# ethernet_poe.net
KiCad netlist of a schematic drawn in EAGLE
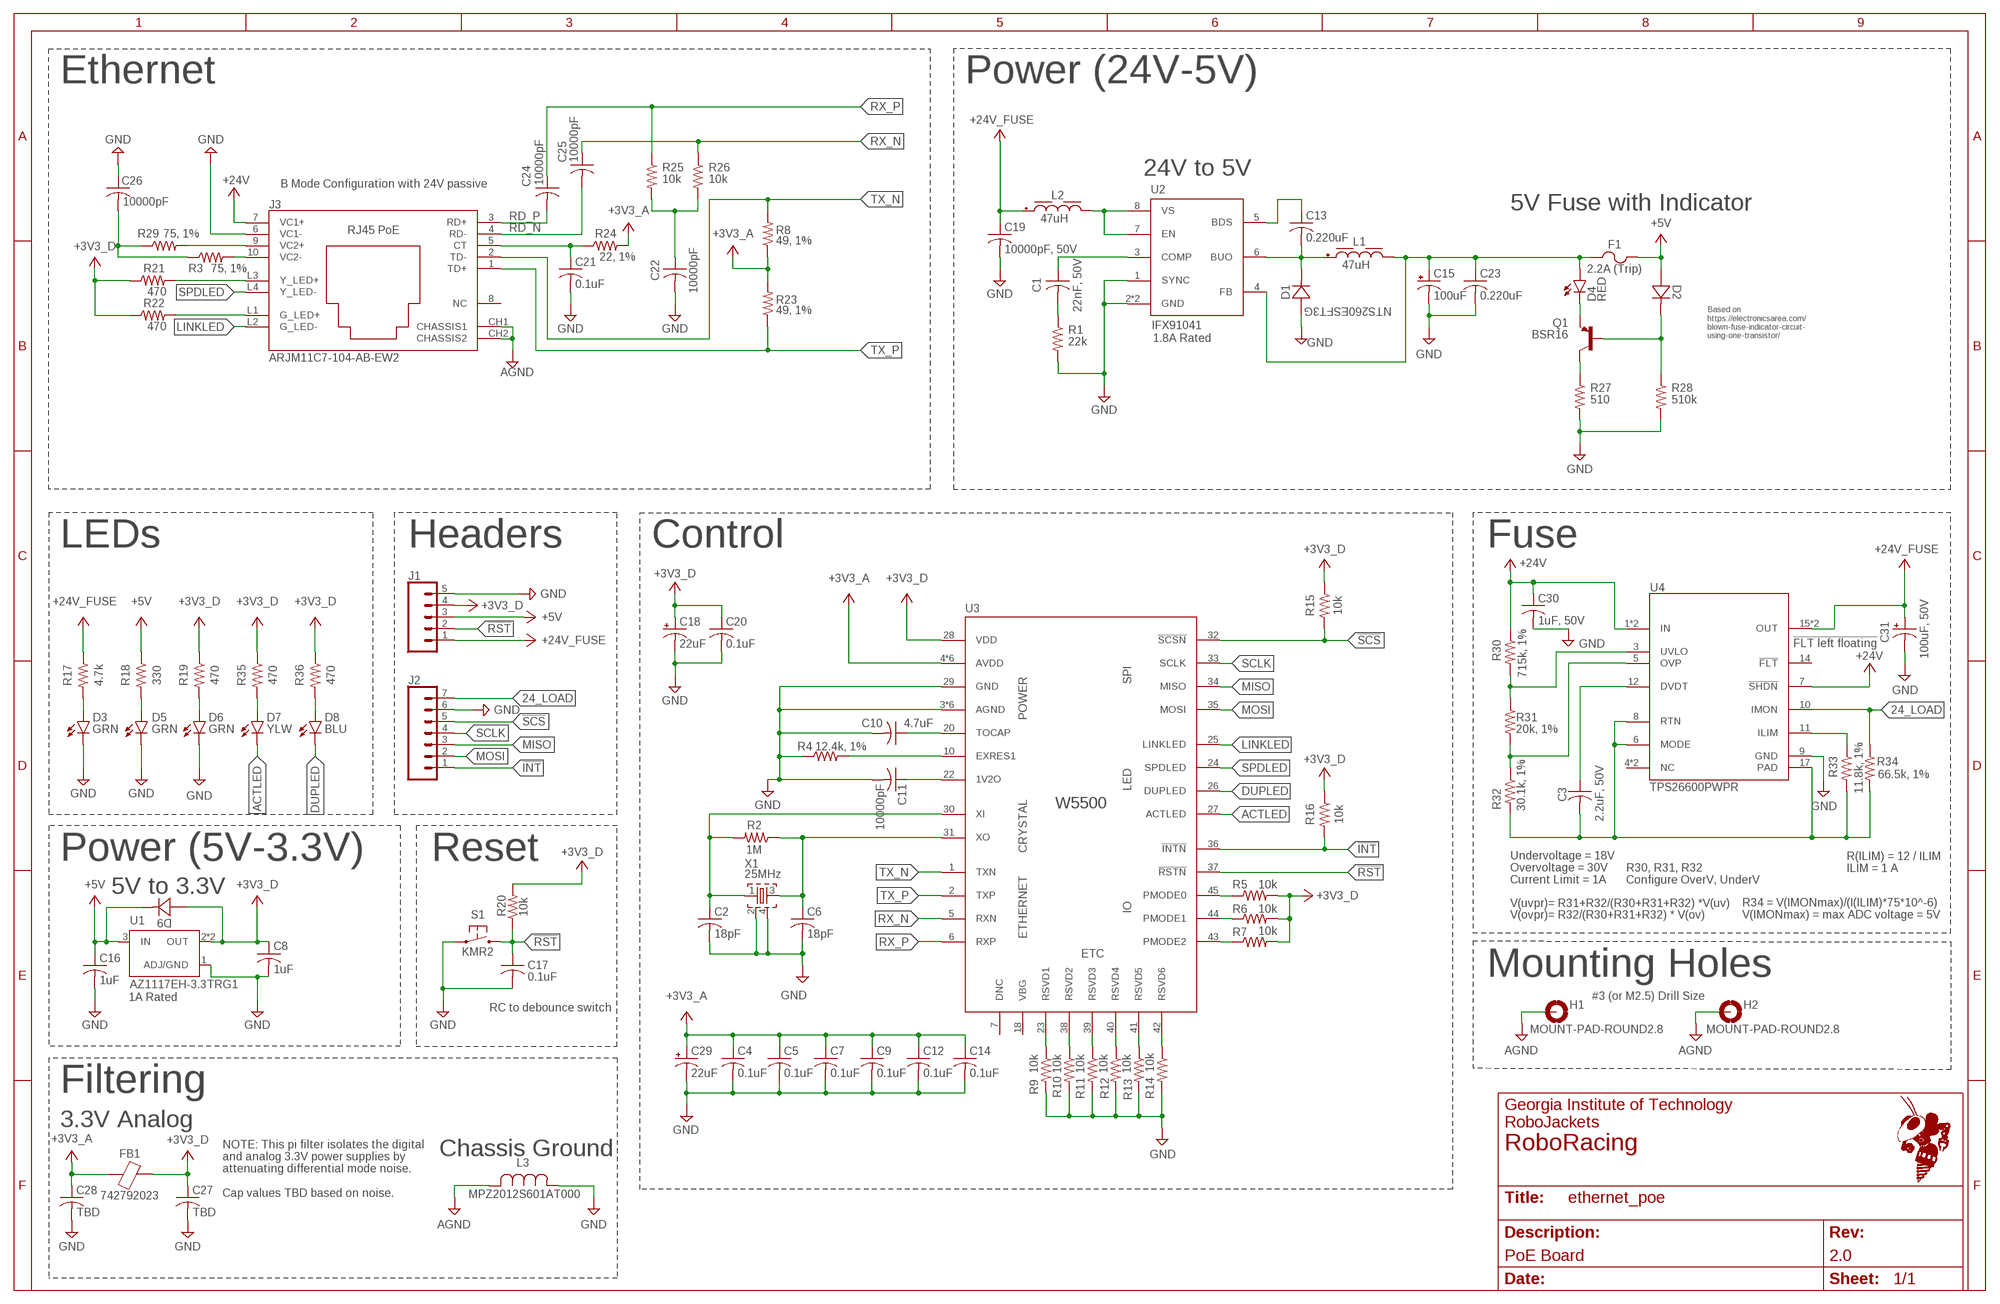
[diagram p0: schematic, sheet 1]

(export (version "E")
  (design (tool "Eeschema 10.0.6"))
  (components
    (comp (ref "C1")
      (value "22nF, 50V")
      (footprint "eagle-import:C0603")
      (libsource (lib "eagle-import") (part "rcl_334_C-USC0603"))
    )
    (comp (ref "C2")
      (value "18pF")
      (footprint "eagle-import:C0603")
      (libsource (lib "eagle-import") (part "rcl_334_C-USC0603"))
    )
    (comp (ref "C3")
      (value "2.2uF, 50V")
      (footprint "eagle-import:C0603")
      (libsource (lib "eagle-import") (part "rcl_334_C-USC0603"))
    )
    (comp (ref "C4")
      (value "0.1uF")
      (footprint "eagle-import:C0402")
      (libsource (lib "eagle-import") (part "C-USC0402"))
    )
    (comp (ref "C5")
      (value "0.1uF")
      (footprint "eagle-import:C0402")
      (libsource (lib "eagle-import") (part "C-USC0402"))
    )
    (comp (ref "C6")
      (value "18pF")
      (footprint "eagle-import:C0603")
      (libsource (lib "eagle-import") (part "rcl_334_C-USC0603"))
    )
    (comp (ref "C7")
      (value "0.1uF")
      (footprint "eagle-import:C0402")
      (libsource (lib "eagle-import") (part "C-USC0402"))
    )
    (comp (ref "C8")
      (value "1uF")
      (footprint "eagle-import:C0603")
      (libsource (lib "eagle-import") (part "rcl_334_C-USC0603"))
    )
    (comp (ref "C9")
      (value "0.1uF")
      (footprint "eagle-import:C0402")
      (libsource (lib "eagle-import") (part "C-USC0402"))
    )
    (comp (ref "C10")
      (value "4.7uF")
      (footprint "eagle-import:C0603")
      (libsource (lib "eagle-import") (part "rcl_334_C-USC0603"))
    )
    (comp (ref "C11")
      (value "10000pF")
      (footprint "eagle-import:C0402")
      (libsource (lib "eagle-import") (part "C-USC0402"))
    )
    (comp (ref "C12")
      (value "0.1uF")
      (footprint "eagle-import:C0402")
      (libsource (lib "eagle-import") (part "C-USC0402"))
    )
    (comp (ref "C13")
      (value "0.220uF")
      (footprint "eagle-import:C0603")
      (libsource (lib "eagle-import") (part "rcl_334_C-USC0603"))
    )
    (comp (ref "C14")
      (value "0.1uF")
      (footprint "eagle-import:C0402")
      (libsource (lib "eagle-import") (part "C-USC0402"))
    )
    (comp (ref "C15")
      (value "100uF")
      (footprint "eagle-import:E2-5")
      (libsource (lib "eagle-import") (part "CPOL-USE2-5"))
    )
    (comp (ref "C16")
      (value "1uF")
      (footprint "eagle-import:C0603")
      (libsource (lib "eagle-import") (part "rcl_334_C-USC0603"))
    )
    (comp (ref "C17")
      (value "0.1uF")
      (footprint "eagle-import:C0603")
      (libsource (lib "eagle-import") (part "rcl_334_C-USC0603"))
    )
    (comp (ref "C18")
      (value "22uF")
      (footprint "eagle-import:E2-5")
      (libsource (lib "eagle-import") (part "CPOL-USE2-5"))
    )
    (comp (ref "C19")
      (value "10000pF, 50V")
      (footprint "eagle-import:C0603")
      (libsource (lib "eagle-import") (part "rcl_334_C-USC0603"))
    )
    (comp (ref "C20")
      (value "0.1uF")
      (footprint "eagle-import:C0603")
      (libsource (lib "eagle-import") (part "rcl_334_C-USC0603"))
    )
    (comp (ref "C21")
      (value "0.1uF")
      (footprint "eagle-import:C0603")
      (libsource (lib "eagle-import") (part "rcl_334_C-USC0603"))
    )
    (comp (ref "C22")
      (value "10000pF")
      (footprint "eagle-import:C0603")
      (libsource (lib "eagle-import") (part "rcl_334_C-USC0603"))
    )
    (comp (ref "C23")
      (value "0.220uF")
      (footprint "eagle-import:C0603")
      (libsource (lib "eagle-import") (part "rcl_334_C-USC0603"))
    )
    (comp (ref "C24")
      (value "10000pF")
      (footprint "eagle-import:C0402")
      (libsource (lib "eagle-import") (part "C-USC0402"))
    )
    (comp (ref "C25")
      (value "10000pF")
      (footprint "eagle-import:C0402")
      (libsource (lib "eagle-import") (part "C-USC0402"))
    )
    (comp (ref "C26")
      (value "10000pF")
      (footprint "eagle-import:C0603")
      (libsource (lib "eagle-import") (part "rcl_334_C-USC0603"))
    )
    (comp (ref "C27")
      (value "TBD")
      (footprint "eagle-import:C0603")
      (libsource (lib "eagle-import") (part "C-USC0603"))
    )
    (comp (ref "C28")
      (value "TBD")
      (footprint "eagle-import:C0603")
      (libsource (lib "eagle-import") (part "C-USC0603"))
    )
    (comp (ref "C29")
      (value "22uF")
      (footprint "eagle-import:PANASONIC_C")
      (libsource (lib "eagle-import") (part "22UF-POLAR-PANASONIC_C-35V-20%"))
    )
    (comp (ref "C30")
      (value "1uF, 50V")
      (footprint "eagle-import:C0603")
      (libsource (lib "eagle-import") (part "rcl_334_C-USC0603"))
    )
    (comp (ref "C31")
      (value "100uF, 50V")
      (footprint "eagle-import:E2-5")
      (libsource (lib "eagle-import") (part "CPOL-USE2-5"))
    )
    (comp (ref "D1")
      (value "NTS260ESFT3G")
      (footprint "eagle-import:DIO_SS26FL")
      (libsource (lib "eagle-import") (part "NTS260ESFT3G"))
    )
    (comp (ref "D2")
      (value "1N4148W-7-F")
      (footprint "eagle-import:SOD123_DIO")
      (libsource (lib "eagle-import") (part "1N4148W-7-F"))
    )
    (comp (ref "D3")
      (value "GRN")
      (footprint "eagle-import:CHIP-LED0603")
      (libsource (lib "eagle-import") (part "LEDCHIP-LED0603"))
    )
    (comp (ref "D4")
      (value "RED")
      (footprint "eagle-import:CHIP-LED0603")
      (libsource (lib "eagle-import") (part "LEDCHIP-LED0603"))
    )
    (comp (ref "D5")
      (value "GRN")
      (footprint "eagle-import:CHIP-LED0603")
      (libsource (lib "eagle-import") (part "LEDCHIP-LED0603"))
    )
    (comp (ref "D6")
      (value "GRN")
      (footprint "eagle-import:CHIP-LED0603")
      (libsource (lib "eagle-import") (part "LEDCHIP-LED0603"))
    )
    (comp (ref "D7")
      (value "YLW")
      (footprint "eagle-import:CHIP-LED0603")
      (libsource (lib "eagle-import") (part "LEDCHIP-LED0603"))
    )
    (comp (ref "D8")
      (value "BLU")
      (footprint "eagle-import:CHIP-LED0603")
      (libsource (lib "eagle-import") (part "LEDCHIP-LED0603"))
    )
    (comp (ref "D9")
      (value "1N4148W-7-F")
      (footprint "eagle-import:SOD123_DIO")
      (libsource (lib "eagle-import") (part "1N4148W-7-F"))
    )
    (comp (ref "F1")
      (value "2.2A (Trip)")
      (footprint "eagle-import:0ZCG_BEL")
      (libsource (lib "eagle-import") (part "0ZCG0110AF2C"))
    )
    (comp (ref "FB1")
      (value "742792023")
      (footprint "eagle-import:0805")
      (libsource (lib "eagle-import") (part "742792023"))
    )
    (comp (ref "H1")
      (value "MOUNT-PAD-ROUND2.8")
      (footprint "eagle-import:2,8-PAD")
      (libsource (lib "eagle-import") (part "MOUNT-PAD-ROUND2.8"))
    )
    (comp (ref "H2")
      (value "MOUNT-PAD-ROUND2.8")
      (footprint "eagle-import:2,8-PAD")
      (libsource (lib "eagle-import") (part "MOUNT-PAD-ROUND2.8"))
    )
    (comp (ref "J1")
      (value "CONN_05")
      (footprint "eagle-import:1X05")
      (libsource (lib "eagle-import") (part "CONN_05"))
    )
    (comp (ref "J2")
      (value "CONN_07")
      (footprint "eagle-import:1X07")
      (libsource (lib "eagle-import") (part "CONN_07"))
    )
    (comp (ref "J3")
      (value "ARJM11C7-104-AB-EW2")
      (footprint "eagle-import:CONN_EW_ABR")
      (libsource (lib "eagle-import") (part "ARJM11C7-104-AB-EW2"))
    )
    (comp (ref "L1")
      (value "47uH")
      (footprint "eagle-import:WE-PD_1260")
      (libsource (lib "eagle-import") (part "WE-PD_1260_744771147"))
    )
    (comp (ref "L2")
      (value "47uH")
      (footprint "eagle-import:WE-PD_7345")
      (libsource (lib "eagle-import") (part "WE-PD_7345_744777147"))
    )
    (comp (ref "L3")
      (value "MPZ2012S601AT000")
      (footprint "eagle-import:IND_2012_TDK")
      (libsource (lib "eagle-import") (part "MPZ2012S601AT000"))
    )
    (comp (ref "Q1")
      (value "BSR16")
      (footprint "eagle-import:SOT-23-3")
      (libsource (lib "eagle-import") (part "BSR16"))
    )
    (comp (ref "R1")
      (value "22k")
      (footprint "eagle-import:R0603")
      (libsource (lib "eagle-import") (part "rcl_334_R-US_R0603"))
    )
    (comp (ref "R2")
      (value "1M")
      (footprint "eagle-import:R0402")
      (libsource (lib "eagle-import") (part "R-US_R0402"))
    )
    (comp (ref "R3")
      (value "75, 1%")
      (footprint "eagle-import:R0603")
      (libsource (lib "eagle-import") (part "rcl_334_R-US_R0603"))
    )
    (comp (ref "R4")
      (value "12.4k, 1%")
      (footprint "eagle-import:R0603")
      (libsource (lib "eagle-import") (part "rcl_334_R-US_R0603"))
    )
    (comp (ref "R5")
      (value "10k")
      (footprint "eagle-import:R0603")
      (libsource (lib "eagle-import") (part "rcl_334_R-US_R0603"))
    )
    (comp (ref "R6")
      (value "10k")
      (footprint "eagle-import:R0603")
      (libsource (lib "eagle-import") (part "rcl_334_R-US_R0603"))
    )
    (comp (ref "R7")
      (value "10k")
      (footprint "eagle-import:R0603")
      (libsource (lib "eagle-import") (part "rcl_334_R-US_R0603"))
    )
    (comp (ref "R8")
      (value "49, 1%")
      (footprint "eagle-import:R0402")
      (libsource (lib "eagle-import") (part "R-US_R0402"))
    )
    (comp (ref "R9")
      (value "10k")
      (footprint "eagle-import:R0603")
      (libsource (lib "eagle-import") (part "rcl_334_R-US_R0603"))
    )
    (comp (ref "R10")
      (value "10k")
      (footprint "eagle-import:R0603")
      (libsource (lib "eagle-import") (part "rcl_334_R-US_R0603"))
    )
    (comp (ref "R11")
      (value "10k")
      (footprint "eagle-import:R0603")
      (libsource (lib "eagle-import") (part "rcl_334_R-US_R0603"))
    )
    (comp (ref "R12")
      (value "10k")
      (footprint "eagle-import:R0603")
      (libsource (lib "eagle-import") (part "rcl_334_R-US_R0603"))
    )
    (comp (ref "R13")
      (value "10k")
      (footprint "eagle-import:R0603")
      (libsource (lib "eagle-import") (part "rcl_334_R-US_R0603"))
    )
    (comp (ref "R14")
      (value "10k")
      (footprint "eagle-import:R0603")
      (libsource (lib "eagle-import") (part "rcl_334_R-US_R0603"))
    )
    (comp (ref "R15")
      (value "10k")
      (footprint "eagle-import:R0603")
      (libsource (lib "eagle-import") (part "rcl_334_R-US_R0603"))
    )
    (comp (ref "R16")
      (value "10k")
      (footprint "eagle-import:R0603")
      (libsource (lib "eagle-import") (part "rcl_334_R-US_R0603"))
    )
    (comp (ref "R17")
      (value "4.7k")
      (footprint "eagle-import:R0603")
      (libsource (lib "eagle-import") (part "rcl_334_R-US_R0603"))
    )
    (comp (ref "R18")
      (value "330")
      (footprint "eagle-import:R0603")
      (libsource (lib "eagle-import") (part "rcl_334_R-US_R0603"))
    )
    (comp (ref "R19")
      (value "470")
      (footprint "eagle-import:R0603")
      (libsource (lib "eagle-import") (part "rcl_334_R-US_R0603"))
    )
    (comp (ref "R20")
      (value "10k")
      (footprint "eagle-import:R0603")
      (libsource (lib "eagle-import") (part "rcl_334_R-US_R0603"))
    )
    (comp (ref "R21")
      (value "470")
      (footprint "eagle-import:R0603")
      (libsource (lib "eagle-import") (part "rcl_334_R-US_R0603"))
    )
    (comp (ref "R22")
      (value "470")
      (footprint "eagle-import:R0603")
      (libsource (lib "eagle-import") (part "rcl_334_R-US_R0603"))
    )
    (comp (ref "R23")
      (value "49, 1%")
      (footprint "eagle-import:R0402")
      (libsource (lib "eagle-import") (part "R-US_R0402"))
    )
    (comp (ref "R24")
      (value "22, 1%")
      (footprint "eagle-import:R0603")
      (libsource (lib "eagle-import") (part "rcl_334_R-US_R0603"))
    )
    (comp (ref "R25")
      (value "10k")
      (footprint "eagle-import:R0603")
      (libsource (lib "eagle-import") (part "rcl_334_R-US_R0603"))
    )
    (comp (ref "R26")
      (value "10k")
      (footprint "eagle-import:R0603")
      (libsource (lib "eagle-import") (part "rcl_334_R-US_R0603"))
    )
    (comp (ref "R27")
      (value "510")
      (footprint "eagle-import:R0603")
      (libsource (lib "eagle-import") (part "rcl_334_R-US_R0603"))
    )
    (comp (ref "R28")
      (value "510k")
      (footprint "eagle-import:R0603")
      (libsource (lib "eagle-import") (part "rcl_334_R-US_R0603"))
    )
    (comp (ref "R29")
      (value "75, 1%")
      (footprint "eagle-import:R0603")
      (libsource (lib "eagle-import") (part "rcl_334_R-US_R0603"))
    )
    (comp (ref "R30")
      (value "715k, 1%")
      (footprint "eagle-import:R0603")
      (libsource (lib "eagle-import") (part "rcl_334_R-US_R0603"))
    )
    (comp (ref "R31")
      (value "20k, 1%")
      (footprint "eagle-import:R0603")
      (libsource (lib "eagle-import") (part "rcl_334_R-US_R0603"))
    )
    (comp (ref "R32")
      (value "30.1k, 1%")
      (footprint "eagle-import:R0603")
      (libsource (lib "eagle-import") (part "rcl_334_R-US_R0603"))
    )
    (comp (ref "R33")
      (value "11.8k, 1%")
      (footprint "eagle-import:R0603")
      (libsource (lib "eagle-import") (part "rcl_334_R-US_R0603"))
    )
    (comp (ref "R34")
      (value "66.5k, 1%")
      (footprint "eagle-import:R0603")
      (libsource (lib "eagle-import") (part "rcl_334_R-US_R0603"))
    )
    (comp (ref "R35")
      (value "470")
      (footprint "eagle-import:R0603")
      (libsource (lib "eagle-import") (part "rcl_334_R-US_R0603"))
    )
    (comp (ref "R36")
      (value "470")
      (footprint "eagle-import:R0603")
      (libsource (lib "eagle-import") (part "rcl_334_R-US_R0603"))
    )
    (comp (ref "S1")
      (value "KMR2")
      (footprint "eagle-import:KMR2")
      (libsource (lib "eagle-import") (part "KMR2"))
    )
    (comp (ref "U1")
      (value "AZ1117EH-3.3TRG1")
      (footprint "eagle-import:SOT230P700X180-4N")
      (libsource (lib "eagle-import") (part "AZ1117EH-3.3TRG1"))
    )
    (comp (ref "U2")
      (value "IFX91041")
      (footprint "eagle-import:SOIC-8-EXPOSED_PAD")
      (libsource (lib "eagle-import") (part "IFX91041"))
    )
    (comp (ref "U3")
      (value "W5500")
      (footprint "eagle-import:48-LQFP")
      (libsource (lib "eagle-import") (part "W5500"))
    )
    (comp (ref "U4")
      (value "TPS26600PWPR")
      (footprint "eagle-import:PWP0016H_N")
      (libsource (lib "eagle-import") (part "TPS26600PWPR"))
    )
    (comp (ref "X1")
      (value "25MHz")
      (footprint "eagle-import:OSCILLATOR-SMD-2.5X2")
      (libsource (lib "eagle-import") (part "ABM10-25.000MHZ-18-E30-T3"))
    )
  )
  (nets
    (net (code "1") (name "+3V3_A") (class "Default")
      (node (ref "C12") (pin "1") (pinfunction "1_1") (pintype "passive"))
      (node (ref "C14") (pin "1") (pinfunction "1_1") (pintype "passive"))
      (node (ref "C28") (pin "1") (pinfunction "1_1") (pintype "passive"))
      (node (ref "C29") (pin "+") (pinfunction "+_+") (pintype "passive"))
      (node (ref "C4") (pin "1") (pinfunction "1_1") (pintype "passive"))
      (node (ref "C5") (pin "1") (pinfunction "1_1") (pintype "passive"))
      (node (ref "C7") (pin "1") (pinfunction "1_1") (pintype "passive"))
      (node (ref "C9") (pin "1") (pinfunction "1_1") (pintype "passive"))
      (node (ref "FB1") (pin "1") (pinfunction "1_1") (pintype "passive"))
      (node (ref "R23") (pin "2") (pinfunction "2_2") (pintype "passive"))
      (node (ref "R24") (pin "2") (pinfunction "2_2") (pintype "passive"))
      (node (ref "R8") (pin "1") (pinfunction "1_1") (pintype "passive"))
      (node (ref "U3") (pin "11") (pinfunction "AVDD_11") (pintype "power_in"))
      (node (ref "U3") (pin "15") (pinfunction "AVDD_15") (pintype "power_in"))
      (node (ref "U3") (pin "17") (pinfunction "AVDD_17") (pintype "power_in"))
      (node (ref "U3") (pin "21") (pinfunction "AVDD_21") (pintype "power_in"))
      (node (ref "U3") (pin "4") (pinfunction "AVDD_4") (pintype "power_in"))
      (node (ref "U3") (pin "8") (pinfunction "AVDD_8") (pintype "power_in"))
    )
    (net (code "2") (name "+3V3_D") (class "Default")
      (node (ref "C18") (pin "+") (pinfunction "+_+") (pintype "passive"))
      (node (ref "C20") (pin "1") (pinfunction "1_1") (pintype "passive"))
      (node (ref "C27") (pin "1") (pinfunction "1_1") (pintype "passive"))
      (node (ref "C8") (pin "1") (pinfunction "1_1") (pintype "passive"))
      (node (ref "D9") (pin "2") (pinfunction "2_2") (pintype "passive"))
      (node (ref "FB1") (pin "2") (pinfunction "2_2") (pintype "passive"))
      (node (ref "J1") (pin "4") (pinfunction "4_4") (pintype "passive"))
      (node (ref "R15") (pin "1") (pinfunction "1_1") (pintype "passive"))
      (node (ref "R16") (pin "1") (pinfunction "1_1") (pintype "passive"))
      (node (ref "R19") (pin "1") (pinfunction "1_1") (pintype "passive"))
      (node (ref "R20") (pin "2") (pinfunction "2_2") (pintype "passive"))
      (node (ref "R21") (pin "1") (pinfunction "1_1") (pintype "passive"))
      (node (ref "R22") (pin "1") (pinfunction "1_1") (pintype "passive"))
      (node (ref "R35") (pin "1") (pinfunction "1_1") (pintype "passive"))
      (node (ref "R36") (pin "1") (pinfunction "1_1") (pintype "passive"))
      (node (ref "R5") (pin "2") (pinfunction "2_2") (pintype "passive"))
      (node (ref "R6") (pin "2") (pinfunction "2_2") (pintype "passive"))
      (node (ref "R7") (pin "2") (pinfunction "2_2") (pintype "passive"))
      (node (ref "U1") (pin "2") (pinfunction "OUT_2") (pintype "output"))
      (node (ref "U1") (pin "4") (pinfunction "OUT_4") (pintype "output"))
      (node (ref "U3") (pin "28") (pinfunction "VDD_28") (pintype "power_in"))
    )
    (net (code "3") (name "+5V") (class "Default")
      (node (ref "C16") (pin "1") (pinfunction "1_1") (pintype "passive"))
      (node (ref "D2") (pin "2") (pinfunction "2_2") (pintype "passive"))
      (node (ref "D9") (pin "1") (pinfunction "1_1") (pintype "passive"))
      (node (ref "F1") (pin "2") (pinfunction "2_2") (pintype "passive"))
      (node (ref "J1") (pin "3") (pinfunction "3_3") (pintype "passive"))
      (node (ref "R18") (pin "1") (pinfunction "1_1") (pintype "passive"))
      (node (ref "U1") (pin "3") (pinfunction "IN_3") (pintype "input"))
    )
    (net (code "4") (name "+24V") (class "Default")
      (node (ref "C30") (pin "1") (pinfunction "1_1") (pintype "passive"))
      (node (ref "J3") (pin "7") (pinfunction "VC1+_7") (pintype "passive"))
      (node (ref "R30") (pin "1") (pinfunction "1_1") (pintype "passive"))
      (node (ref "U4") (pin "1") (pinfunction "IN_1") (pintype "power_in"))
      (node (ref "U4") (pin "2") (pinfunction "IN_2") (pintype "power_in"))
      (node (ref "U4") (pin "7") (pinfunction "~{SHDN}_7") (pintype "input"))
    )
    (net (code "5") (name "+24V_FUSE") (class "Default")
      (node (ref "C19") (pin "1") (pinfunction "1_1") (pintype "passive"))
      (node (ref "C31") (pin "+") (pinfunction "+_+") (pintype "passive"))
      (node (ref "J1") (pin "1") (pinfunction "1_1") (pintype "passive"))
      (node (ref "L2") (pin "1") (pinfunction "1_1") (pintype "passive"))
      (node (ref "R17") (pin "1") (pinfunction "1_1") (pintype "passive"))
      (node (ref "U4") (pin "15") (pinfunction "OUT_15") (pintype "power_in"))
      (node (ref "U4") (pin "16") (pinfunction "OUT_16") (pintype "power_in"))
    )
    (net (code "6") (name "/RD_N") (class "Default")
      (node (ref "C25") (pin "2") (pinfunction "2_2") (pintype "passive"))
      (node (ref "J3") (pin "4") (pinfunction "RD-_4") (pintype "passive"))
    )
    (net (code "7") (name "/RD_P") (class "Default")
      (node (ref "C24") (pin "2") (pinfunction "2_2") (pintype "passive"))
      (node (ref "J3") (pin "3") (pinfunction "RD+_3") (pintype "passive"))
    )
    (net (code "8") (name "/~{INT}") (class "Default")
      (node (ref "J2") (pin "1") (pinfunction "1_1") (pintype "passive"))
      (node (ref "R16") (pin "2") (pinfunction "2_2") (pintype "passive"))
      (node (ref "U3") (pin "36") (pinfunction "~{INTN}_36") (pintype "output"))
    )
    (net (code "9") (name "/~{RST}") (class "Default")
      (node (ref "C17") (pin "1") (pinfunction "1_1") (pintype "passive"))
      (node (ref "J1") (pin "2") (pinfunction "2_2") (pintype "passive"))
      (node (ref "R20") (pin "1") (pinfunction "1_1") (pintype "passive"))
      (node (ref "S1") (pin "2.1") (pinfunction "2_2.1") (pintype "passive"))
      (node (ref "S1") (pin "2.2") (pinfunction "2_2.2") (pintype "passive"))
      (node (ref "U3") (pin "37") (pinfunction "~{RSTN}_37") (pintype "input"))
    )
    (net (code "10") (name "/~{SCS}") (class "Default")
      (node (ref "J2") (pin "5") (pinfunction "5_5") (pintype "passive"))
      (node (ref "R15") (pin "2") (pinfunction "2_2") (pintype "passive"))
      (node (ref "U3") (pin "32") (pinfunction "~{SCSN}_32") (pintype "input"))
    )
    (net (code "11") (name "24_LOAD") (class "Default")
      (node (ref "J2") (pin "7") (pinfunction "7_7") (pintype "passive"))
      (node (ref "R34") (pin "1") (pinfunction "1_1") (pintype "passive"))
      (node (ref "U4") (pin "10") (pinfunction "IMON_10") (pintype "output"))
    )
    (net (code "12") (name "ACTLED") (class "Default")
      (node (ref "D7") (pin "C") (pinfunction "C_C") (pintype "passive"))
      (node (ref "U3") (pin "27") (pinfunction "ACTLED_27") (pintype "output"))
    )
    (net (code "13") (name "AGND") (class "Default")
      (node (ref "H1") (pin "B2,8") (pinfunction "MOUNT_B2,8") (pintype "passive"))
      (node (ref "H2") (pin "B2,8") (pinfunction "MOUNT_B2,8") (pintype "passive"))
      (node (ref "J3") (pin "CH1") (pinfunction "CHASSIS1_CH1") (pintype "passive"))
      (node (ref "J3") (pin "CH2") (pinfunction "CHASSIS2_CH2") (pintype "passive"))
      (node (ref "L3") (pin "2") (pinfunction "2_2") (pintype "passive"))
    )
    (net (code "14") (name "DUPLED") (class "Default")
      (node (ref "D8") (pin "C") (pinfunction "C_C") (pintype "passive"))
      (node (ref "U3") (pin "26") (pinfunction "DUPLED_26") (pintype "output"))
    )
    (net (code "15") (name "GND") (class "Default")
      (node (ref "C10") (pin "2") (pinfunction "2_2") (pintype "passive"))
      (node (ref "C11") (pin "2") (pinfunction "2_2") (pintype "passive"))
      (node (ref "C12") (pin "2") (pinfunction "2_2") (pintype "passive"))
      (node (ref "C14") (pin "2") (pinfunction "2_2") (pintype "passive"))
      (node (ref "C15") (pin "-") (pinfunction "-_-") (pintype "passive"))
      (node (ref "C16") (pin "2") (pinfunction "2_2") (pintype "passive"))
      (node (ref "C17") (pin "2") (pinfunction "2_2") (pintype "passive"))
      (node (ref "C18") (pin "-") (pinfunction "-_-") (pintype "passive"))
      (node (ref "C19") (pin "2") (pinfunction "2_2") (pintype "passive"))
      (node (ref "C2") (pin "2") (pinfunction "2_2") (pintype "passive"))
      (node (ref "C20") (pin "2") (pinfunction "2_2") (pintype "passive"))
      (node (ref "C21") (pin "2") (pinfunction "2_2") (pintype "passive"))
      (node (ref "C22") (pin "2") (pinfunction "2_2") (pintype "passive"))
      (node (ref "C23") (pin "2") (pinfunction "2_2") (pintype "passive"))
      (node (ref "C26") (pin "1") (pinfunction "1_1") (pintype "passive"))
      (node (ref "C27") (pin "2") (pinfunction "2_2") (pintype "passive"))
      (node (ref "C28") (pin "2") (pinfunction "2_2") (pintype "passive"))
      (node (ref "C29") (pin "-") (pinfunction "-_-") (pintype "passive"))
      (node (ref "C30") (pin "2") (pinfunction "2_2") (pintype "passive"))
      (node (ref "C31") (pin "-") (pinfunction "-_-") (pintype "passive"))
      (node (ref "C4") (pin "2") (pinfunction "2_2") (pintype "passive"))
      (node (ref "C5") (pin "2") (pinfunction "2_2") (pintype "passive"))
      (node (ref "C6") (pin "2") (pinfunction "2_2") (pintype "passive"))
      (node (ref "C7") (pin "2") (pinfunction "2_2") (pintype "passive"))
      (node (ref "C8") (pin "2") (pinfunction "2_2") (pintype "passive"))
      (node (ref "C9") (pin "2") (pinfunction "2_2") (pintype "passive"))
      (node (ref "D1") (pin "2") (pinfunction "2_2") (pintype "passive"))
      (node (ref "D3") (pin "C") (pinfunction "C_C") (pintype "passive"))
      (node (ref "D5") (pin "C") (pinfunction "C_C") (pintype "passive"))
      (node (ref "D6") (pin "C") (pinfunction "C_C") (pintype "passive"))
      (node (ref "J1") (pin "5") (pinfunction "5_5") (pintype "passive"))
      (node (ref "J2") (pin "6") (pinfunction "6_6") (pintype "passive"))
      (node (ref "J3") (pin "6") (pinfunction "VC1-_6") (pintype "passive"))
      (node (ref "L3") (pin "1") (pinfunction "1_1") (pintype "passive"))
      (node (ref "R1") (pin "2") (pinfunction "2_2") (pintype "passive"))
      (node (ref "R10") (pin "2") (pinfunction "2_2") (pintype "passive"))
      (node (ref "R11") (pin "2") (pinfunction "2_2") (pintype "passive"))
      (node (ref "R12") (pin "2") (pinfunction "2_2") (pintype "passive"))
      (node (ref "R13") (pin "2") (pinfunction "2_2") (pintype "passive"))
      (node (ref "R14") (pin "2") (pinfunction "2_2") (pintype "passive"))
      (node (ref "R27") (pin "2") (pinfunction "2_2") (pintype "passive"))
      (node (ref "R28") (pin "2") (pinfunction "2_2") (pintype "passive"))
      (node (ref "R4") (pin "1") (pinfunction "1_1") (pintype "passive"))
      (node (ref "R9") (pin "2") (pinfunction "2_2") (pintype "passive"))
      (node (ref "S1") (pin "1.1") (pinfunction "1_1.1") (pintype "passive"))
      (node (ref "S1") (pin "1.2") (pinfunction "1_1.2") (pintype "passive"))
      (node (ref "U1") (pin "1") (pinfunction "ADJ/GND_1") (pintype "power_in"))
      (node (ref "U2") (pin "1") (pinfunction "SYNC_1") (pintype "input"))
      (node (ref "U2") (pin "2") (pinfunction "GND_2") (pintype "power_in"))
      (node (ref "U2") (pin "9") (pinfunction "GND_9") (pintype "power_in"))
      (node (ref "U3") (pin "14") (pinfunction "AGND_14") (pintype "power_in"))
      (node (ref "U3") (pin "16") (pinfunction "AGND_16") (pintype "power_in"))
      (node (ref "U3") (pin "19") (pinfunction "AGND_19") (pintype "power_in"))
      (node (ref "U3") (pin "29") (pinfunction "GND_29") (pintype "power_in"))
      (node (ref "U3") (pin "3") (pinfunction "AGND_3") (pintype "power_in"))
      (node (ref "U3") (pin "48") (pinfunction "AGND_48") (pintype "power_in"))
      (node (ref "U3") (pin "9") (pinfunction "AGND_9") (pintype "power_in"))
      (node (ref "U4") (pin "9") (pinfunction "GND_9") (pintype "power_in"))
      (node (ref "X1") (pin "2") (pinfunction "SHD1_2") (pintype "passive"))
      (node (ref "X1") (pin "4") (pinfunction "SHD2_4") (pintype "passive"))
    )
    (net (code "16") (name "LINKLED") (class "Default")
      (node (ref "J3") (pin "L2") (pinfunction "G_LED-_L2") (pintype "passive"))
      (node (ref "U3") (pin "25") (pinfunction "LINKLED_25") (pintype "output"))
    )
    (net (code "17") (name "MISO") (class "Default")
      (node (ref "J2") (pin "3") (pinfunction "3_3") (pintype "passive"))
      (node (ref "U3") (pin "34") (pinfunction "MISO_34") (pintype "output"))
    )
    (net (code "18") (name "MOSI") (class "Default")
      (node (ref "J2") (pin "2") (pinfunction "2_2") (pintype "passive"))
      (node (ref "U3") (pin "35") (pinfunction "MOSI_35") (pintype "input"))
    )
    (net (code "19") (name "Net-(C1-Pad2)") (class "Default")
      (node (ref "C1") (pin "2") (pinfunction "2_2") (pintype "passive"))
      (node (ref "R1") (pin "1") (pinfunction "1_1") (pintype "passive"))
    )
    (net (code "20") (name "Net-(C22-Pad1)") (class "Default")
      (node (ref "C22") (pin "1") (pinfunction "1_1") (pintype "passive"))
      (node (ref "R25") (pin "2") (pinfunction "2_2") (pintype "passive"))
      (node (ref "R26") (pin "2") (pinfunction "2_2") (pintype "passive"))
    )
    (net (code "21") (name "Net-(C26-Pad2)") (class "Default")
      (node (ref "C26") (pin "2") (pinfunction "2_2") (pintype "passive"))
      (node (ref "R29") (pin "1") (pinfunction "1_1") (pintype "passive"))
      (node (ref "R3") (pin "1") (pinfunction "1_1") (pintype "passive"))
    )
    (net (code "22") (name "Net-(D3-PadA)") (class "Default")
      (node (ref "D3") (pin "A") (pinfunction "A_A") (pintype "passive"))
      (node (ref "R17") (pin "2") (pinfunction "2_2") (pintype "passive"))
    )
    (net (code "23") (name "Net-(D5-PadA)") (class "Default")
      (node (ref "D5") (pin "A") (pinfunction "A_A") (pintype "passive"))
      (node (ref "R18") (pin "2") (pinfunction "2_2") (pintype "passive"))
    )
    (net (code "24") (name "Net-(D6-PadA)") (class "Default")
      (node (ref "D6") (pin "A") (pinfunction "A_A") (pintype "passive"))
      (node (ref "R19") (pin "2") (pinfunction "2_2") (pintype "passive"))
    )
    (net (code "25") (name "Net-(D7-PadA)") (class "Default")
      (node (ref "D7") (pin "A") (pinfunction "A_A") (pintype "passive"))
      (node (ref "R35") (pin "2") (pinfunction "2_2") (pintype "passive"))
    )
    (net (code "26") (name "Net-(D8-PadA)") (class "Default")
      (node (ref "D8") (pin "A") (pinfunction "A_A") (pintype "passive"))
      (node (ref "R36") (pin "2") (pinfunction "2_2") (pintype "passive"))
    )
    (net (code "27") (name "Net-(J3-CT)") (class "Default")
      (node (ref "C21") (pin "1") (pinfunction "1_1") (pintype "passive"))
      (node (ref "J3") (pin "5") (pinfunction "CT_5") (pintype "passive"))
      (node (ref "R24") (pin "1") (pinfunction "1_1") (pintype "passive"))
    )
    (net (code "28") (name "Net-(J3-G_LED+)") (class "Default")
      (node (ref "J3") (pin "L1") (pinfunction "G_LED+_L1") (pintype "passive"))
      (node (ref "R22") (pin "2") (pinfunction "2_2") (pintype "passive"))
    )
    (net (code "29") (name "Net-(J3-VC2+)") (class "Default")
      (node (ref "J3") (pin "9") (pinfunction "VC2+_9") (pintype "passive"))
      (node (ref "R29") (pin "2") (pinfunction "2_2") (pintype "passive"))
    )
    (net (code "30") (name "Net-(J3-VC2-)") (class "Default")
      (node (ref "J3") (pin "10") (pinfunction "VC2-_10") (pintype "passive"))
      (node (ref "R3") (pin "2") (pinfunction "2_2") (pintype "passive"))
    )
    (net (code "31") (name "Net-(J3-Y_LED+)") (class "Default")
      (node (ref "J3") (pin "L3") (pinfunction "Y_LED+_L3") (pintype "passive"))
      (node (ref "R21") (pin "2") (pinfunction "2_2") (pintype "passive"))
    )
    (net (code "32") (name "Net-(Q1-B)") (class "Default")
      (node (ref "D2") (pin "1") (pinfunction "1_1") (pintype "passive"))
      (node (ref "Q1") (pin "1") (pinfunction "B_1") (pintype "passive"))
      (node (ref "R28") (pin "1") (pinfunction "1_1") (pintype "passive"))
    )
    (net (code "33") (name "Net-(Q1-C)") (class "Default")
      (node (ref "Q1") (pin "3") (pinfunction "C_3") (pintype "passive"))
      (node (ref "R27") (pin "1") (pinfunction "1_1") (pintype "passive"))
    )
    (net (code "34") (name "Net-(Q1-E)") (class "Default")
      (node (ref "D4") (pin "C") (pinfunction "C_C") (pintype "passive"))
      (node (ref "Q1") (pin "2") (pinfunction "E_2") (pintype "passive"))
    )
    (net (code "35") (name "Net-(U2-BDS)") (class "Default")
      (node (ref "C13") (pin "1") (pinfunction "1_1") (pintype "passive"))
      (node (ref "U2") (pin "5") (pinfunction "BDS_5") (pintype "bidirectional"))
    )
    (net (code "36") (name "Net-(U2-BUO)") (class "Default")
      (node (ref "C13") (pin "2") (pinfunction "2_2") (pintype "passive"))
      (node (ref "D1") (pin "1") (pinfunction "1_1") (pintype "passive"))
      (node (ref "L1") (pin "1") (pinfunction "1_1") (pintype "passive"))
      (node (ref "U2") (pin "6") (pinfunction "BUO_6") (pintype "bidirectional"))
    )
    (net (code "37") (name "Net-(U2-COMP)") (class "Default")
      (node (ref "C1") (pin "1") (pinfunction "1_1") (pintype "passive"))
      (node (ref "U2") (pin "3") (pinfunction "COMP_3") (pintype "bidirectional"))
    )
    (net (code "38") (name "Net-(U2-EN)") (class "Default")
      (node (ref "L2") (pin "2") (pinfunction "2_2") (pintype "passive"))
      (node (ref "U2") (pin "7") (pinfunction "EN_7") (pintype "input"))
      (node (ref "U2") (pin "8") (pinfunction "VS_8") (pintype "power_in"))
    )
    (net (code "39") (name "Net-(U2-FB)") (class "Default")
      (node (ref "C15") (pin "+") (pinfunction "+_+") (pintype "passive"))
      (node (ref "C23") (pin "1") (pinfunction "1_1") (pintype "passive"))
      (node (ref "D4") (pin "A") (pinfunction "A_A") (pintype "passive"))
      (node (ref "F1") (pin "1") (pinfunction "1_1") (pintype "passive"))
      (node (ref "L1") (pin "2") (pinfunction "2_2") (pintype "passive"))
      (node (ref "U2") (pin "4") (pinfunction "FB_4") (pintype "bidirectional"))
    )
    (net (code "40") (name "Net-(U3-1V2O)") (class "Default")
      (node (ref "C11") (pin "1") (pinfunction "1_1") (pintype "passive"))
      (node (ref "U3") (pin "22") (pinfunction "1V2O_22") (pintype "output"))
    )
    (net (code "41") (name "Net-(U3-EXRES1)") (class "Default")
      (node (ref "R4") (pin "2") (pinfunction "2_2") (pintype "passive"))
      (node (ref "U3") (pin "10") (pinfunction "EXRES1_10") (pintype "output"))
    )
    (net (code "42") (name "Net-(U3-PMODE0)") (class "Default")
      (node (ref "R5") (pin "1") (pinfunction "1_1") (pintype "passive"))
      (node (ref "U3") (pin "45") (pinfunction "PMODE0_45") (pintype "input"))
    )
    (net (code "43") (name "Net-(U3-PMODE1)") (class "Default")
      (node (ref "R6") (pin "1") (pinfunction "1_1") (pintype "passive"))
      (node (ref "U3") (pin "44") (pinfunction "PMODE1_44") (pintype "input"))
    )
    (net (code "44") (name "Net-(U3-PMODE2)") (class "Default")
      (node (ref "R7") (pin "1") (pinfunction "1_1") (pintype "passive"))
      (node (ref "U3") (pin "43") (pinfunction "PMODE2_43") (pintype "input"))
    )
    (net (code "45") (name "Net-(U3-RSVD1)") (class "Default")
      (node (ref "R9") (pin "1") (pinfunction "1_1") (pintype "passive"))
      (node (ref "U3") (pin "23") (pinfunction "RSVD1_23") (pintype "input"))
    )
    (net (code "46") (name "Net-(U3-RSVD2)") (class "Default")
      (node (ref "R10") (pin "1") (pinfunction "1_1") (pintype "passive"))
      (node (ref "U3") (pin "38") (pinfunction "RSVD2_38") (pintype "input"))
    )
    (net (code "47") (name "Net-(U3-RSVD3)") (class "Default")
      (node (ref "R11") (pin "1") (pinfunction "1_1") (pintype "passive"))
      (node (ref "U3") (pin "39") (pinfunction "RSVD3_39") (pintype "input"))
    )
    (net (code "48") (name "Net-(U3-RSVD4)") (class "Default")
      (node (ref "R12") (pin "1") (pinfunction "1_1") (pintype "passive"))
      (node (ref "U3") (pin "40") (pinfunction "RSVD4_40") (pintype "input"))
    )
    (net (code "49") (name "Net-(U3-RSVD5)") (class "Default")
      (node (ref "R13") (pin "1") (pinfunction "1_1") (pintype "passive"))
      (node (ref "U3") (pin "41") (pinfunction "RSVD5_41") (pintype "input"))
    )
    (net (code "50") (name "Net-(U3-RSVD6)") (class "Default")
      (node (ref "R14") (pin "1") (pinfunction "1_1") (pintype "passive"))
      (node (ref "U3") (pin "42") (pinfunction "RSVD6_42") (pintype "input"))
    )
    (net (code "51") (name "Net-(U3-TOCAP)") (class "Default")
      (node (ref "C10") (pin "1") (pinfunction "1_1") (pintype "passive"))
      (node (ref "U3") (pin "20") (pinfunction "TOCAP_20") (pintype "output"))
    )
    (net (code "52") (name "Net-(U3-XI)") (class "Default")
      (node (ref "C2") (pin "1") (pinfunction "1_1") (pintype "passive"))
      (node (ref "R2") (pin "2") (pinfunction "2_2") (pintype "passive"))
      (node (ref "U3") (pin "30") (pinfunction "XI_30") (pintype "bidirectional"))
      (node (ref "X1") (pin "1") (pinfunction "IN_1") (pintype "passive"))
    )
    (net (code "53") (name "Net-(U3-XO)") (class "Default")
      (node (ref "C6") (pin "1") (pinfunction "1_1") (pintype "passive"))
      (node (ref "R2") (pin "1") (pinfunction "1_1") (pintype "passive"))
      (node (ref "U3") (pin "31") (pinfunction "XO_31") (pintype "bidirectional"))
      (node (ref "X1") (pin "3") (pinfunction "OUT_3") (pintype "passive"))
    )
    (net (code "54") (name "Net-(U4-DVDT)") (class "Default")
      (node (ref "C3") (pin "1") (pinfunction "1_1") (pintype "passive"))
      (node (ref "U4") (pin "12") (pinfunction "DVDT_12") (pintype "input"))
    )
    (net (code "55") (name "Net-(U4-ILIM)") (class "Default")
      (node (ref "R33") (pin "1") (pinfunction "1_1") (pintype "passive"))
      (node (ref "U4") (pin "11") (pinfunction "ILIM_11") (pintype "output"))
    )
    (net (code "56") (name "Net-(U4-MODE)") (class "Default")
      (node (ref "C3") (pin "2") (pinfunction "2_2") (pintype "passive"))
      (node (ref "R32") (pin "2") (pinfunction "2_2") (pintype "passive"))
      (node (ref "R33") (pin "2") (pinfunction "2_2") (pintype "passive"))
      (node (ref "R34") (pin "2") (pinfunction "2_2") (pintype "passive"))
      (node (ref "U4") (pin "17") (pinfunction "PAD_17") (pintype "power_in"))
      (node (ref "U4") (pin "6") (pinfunction "MODE_6") (pintype "input"))
      (node (ref "U4") (pin "8") (pinfunction "RTN_8") (pintype "input"))
    )
    (net (code "57") (name "Net-(U4-OVP)") (class "Default")
      (node (ref "R31") (pin "2") (pinfunction "2_2") (pintype "passive"))
      (node (ref "R32") (pin "1") (pinfunction "1_1") (pintype "passive"))
      (node (ref "U4") (pin "5") (pinfunction "OVP_5") (pintype "input"))
    )
    (net (code "58") (name "Net-(U4-UVLO)") (class "Default")
      (node (ref "R30") (pin "2") (pinfunction "2_2") (pintype "passive"))
      (node (ref "R31") (pin "1") (pinfunction "1_1") (pintype "passive"))
      (node (ref "U4") (pin "3") (pinfunction "UVLO_3") (pintype "input"))
    )
    (net (code "59") (name "RX_N") (class "Default")
      (node (ref "C25") (pin "1") (pinfunction "1_1") (pintype "passive"))
      (node (ref "R26") (pin "1") (pinfunction "1_1") (pintype "passive"))
      (node (ref "U3") (pin "5") (pinfunction "RXN_5") (pintype "input"))
    )
    (net (code "60") (name "RX_P") (class "Default")
      (node (ref "C24") (pin "1") (pinfunction "1_1") (pintype "passive"))
      (node (ref "R25") (pin "1") (pinfunction "1_1") (pintype "passive"))
      (node (ref "U3") (pin "6") (pinfunction "RXP_6") (pintype "input"))
    )
    (net (code "61") (name "SCLK") (class "Default")
      (node (ref "J2") (pin "4") (pinfunction "4_4") (pintype "passive"))
      (node (ref "U3") (pin "33") (pinfunction "SCLK_33") (pintype "input"))
    )
    (net (code "62") (name "SPDLED") (class "Default")
      (node (ref "J3") (pin "L4") (pinfunction "Y_LED-_L4") (pintype "passive"))
      (node (ref "U3") (pin "24") (pinfunction "SPDLED_24") (pintype "output"))
    )
    (net (code "63") (name "TX_N") (class "Default")
      (node (ref "J3") (pin "2") (pinfunction "TD-_2") (pintype "passive"))
      (node (ref "R8") (pin "2") (pinfunction "2_2") (pintype "passive"))
      (node (ref "U3") (pin "1") (pinfunction "TXN_1") (pintype "output"))
    )
    (net (code "64") (name "TX_P") (class "Default")
      (node (ref "J3") (pin "1") (pinfunction "TD+_1") (pintype "passive"))
      (node (ref "R23") (pin "1") (pinfunction "1_1") (pintype "passive"))
      (node (ref "U3") (pin "2") (pinfunction "TXP_2") (pintype "output"))
    )
    (net (code "65") (name "unconnected-(J3-NC-Pad8)") (class "Default")
      (node (ref "J3") (pin "8") (pinfunction "NC_8") (pintype "no_connect"))
    )
    (net (code "66") (name "unconnected-(U3-DNC-Pad7)") (class "Default")
      (node (ref "U3") (pin "7") (pinfunction "DNC_7") (pintype "no_connect"))
    )
    (net (code "67") (name "unconnected-(U3-VBG-Pad18)") (class "Default")
      (node (ref "U3") (pin "18") (pinfunction "VBG_18") (pintype "no_connect"))
    )
    (net (code "68") (name "unconnected-(U4-NC-Pad4)") (class "Default")
      (node (ref "U4") (pin "4") (pinfunction "NC_4") (pintype "no_connect"))
    )
    (net (code "69") (name "unconnected-(U4-NC-Pad13)") (class "Default")
      (node (ref "U4") (pin "13") (pinfunction "NC_13") (pintype "no_connect"))
    )
    (net (code "70") (name "unconnected-(U4-~{FLT}-Pad14)") (class "Default")
      (node (ref "U4") (pin "14") (pinfunction "~{FLT}_14") (pintype "open_collector"))
    )
  )
)
